# Top.net
KiCad netlist of a schematic drawn in Altium Designer
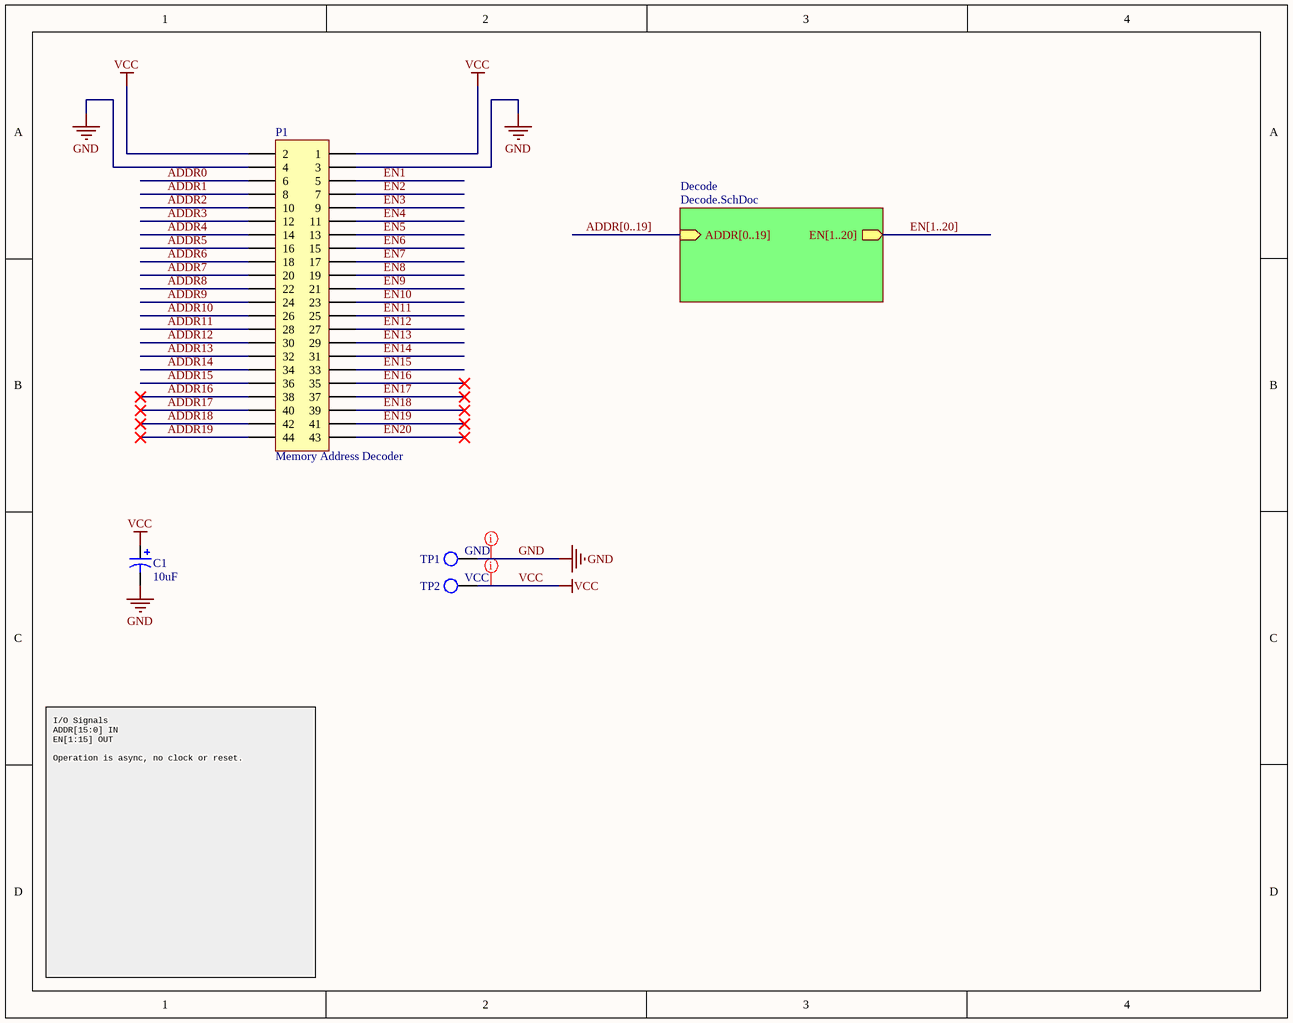
[diagram p0: Top.SchDoc]

(export (version "E")
  (design (tool "Eeschema 10.0.6"))
  (components
    (comp (ref "C1")
      (value "10uF")
      (footprint "C5x7")
      (description "Polarized Capacitor")
      (fields (field (name "Comment") "Cap Pol5") (field (name "PUBLISHER") "Altium Limited"))
      (libsource (lib "Miscellaneous Devices") (part "Cap Pol5"))
    )
    (comp (ref "P1")
      (value "Memory Address Decoder")
      (footprint "HDR2X22H")
      (description "Header, 22-Pin, Dual row, Right Angle")
      (fields (field (name "PUBLISHER") "Altium Limited"))
      (libsource (lib "Miscellaneous Connectors") (part "Header 22X2H"))
    )
    (comp (ref "TP1") (value "GND") (footprint "KSTN-5011_V") (libsource (lib "TP") (part "TP")))
    (comp (ref "TP2") (value "VCC") (footprint "KSTN-5011_V") (libsource (lib "TP") (part "TP")))
  )
  (nets
    (net (code "1") (name "/ADDR0") (class "Default")
      (node (ref "P1") (pin "6") (pinfunction "6_6") (pintype "passive"))
    )
    (net (code "2") (name "/ADDR1") (class "Default")
      (node (ref "P1") (pin "8") (pinfunction "8_8") (pintype "passive"))
    )
    (net (code "3") (name "/ADDR2") (class "Default")
      (node (ref "P1") (pin "10") (pinfunction "10_10") (pintype "passive"))
    )
    (net (code "4") (name "/ADDR3") (class "Default")
      (node (ref "P1") (pin "12") (pinfunction "12_12") (pintype "passive"))
    )
    (net (code "5") (name "/ADDR4") (class "Default")
      (node (ref "P1") (pin "14") (pinfunction "14_14") (pintype "passive"))
    )
    (net (code "6") (name "/ADDR5") (class "Default")
      (node (ref "P1") (pin "16") (pinfunction "16_16") (pintype "passive"))
    )
    (net (code "7") (name "/ADDR6") (class "Default")
      (node (ref "P1") (pin "18") (pinfunction "18_18") (pintype "passive"))
    )
    (net (code "8") (name "/ADDR7") (class "Default")
      (node (ref "P1") (pin "20") (pinfunction "20_20") (pintype "passive"))
    )
    (net (code "9") (name "/ADDR8") (class "Default")
      (node (ref "P1") (pin "22") (pinfunction "22_22") (pintype "passive"))
    )
    (net (code "10") (name "/ADDR9") (class "Default")
      (node (ref "P1") (pin "24") (pinfunction "24_24") (pintype "passive"))
    )
    (net (code "11") (name "/ADDR10") (class "Default")
      (node (ref "P1") (pin "26") (pinfunction "26_26") (pintype "passive"))
    )
    (net (code "12") (name "/ADDR11") (class "Default")
      (node (ref "P1") (pin "28") (pinfunction "28_28") (pintype "passive"))
    )
    (net (code "13") (name "/ADDR12") (class "Default")
      (node (ref "P1") (pin "30") (pinfunction "30_30") (pintype "passive"))
    )
    (net (code "14") (name "/ADDR13") (class "Default")
      (node (ref "P1") (pin "32") (pinfunction "32_32") (pintype "passive"))
    )
    (net (code "15") (name "/ADDR14") (class "Default")
      (node (ref "P1") (pin "34") (pinfunction "34_34") (pintype "passive"))
    )
    (net (code "16") (name "/ADDR15") (class "Default")
      (node (ref "P1") (pin "36") (pinfunction "36_36") (pintype "passive"))
    )
    (net (code "17") (name "/ADDR16") (class "Default")
      (node (ref "P1") (pin "38") (pinfunction "38_38") (pintype "passive+no_connect"))
    )
    (net (code "18") (name "/ADDR17") (class "Default")
      (node (ref "P1") (pin "40") (pinfunction "40_40") (pintype "passive+no_connect"))
    )
    (net (code "19") (name "/ADDR18") (class "Default")
      (node (ref "P1") (pin "42") (pinfunction "42_42") (pintype "passive+no_connect"))
    )
    (net (code "20") (name "/ADDR19") (class "Default")
      (node (ref "P1") (pin "44") (pinfunction "44_44") (pintype "passive+no_connect"))
    )
    (net (code "22") (name "/EN1") (class "Default")
      (node (ref "P1") (pin "5") (pinfunction "5_5") (pintype "passive"))
    )
    (net (code "23") (name "/EN2") (class "Default")
      (node (ref "P1") (pin "7") (pinfunction "7_7") (pintype "passive"))
    )
    (net (code "24") (name "/EN3") (class "Default")
      (node (ref "P1") (pin "9") (pinfunction "9_9") (pintype "passive"))
    )
    (net (code "25") (name "/EN4") (class "Default")
      (node (ref "P1") (pin "11") (pinfunction "11_11") (pintype "passive"))
    )
    (net (code "26") (name "/EN5") (class "Default")
      (node (ref "P1") (pin "13") (pinfunction "13_13") (pintype "passive"))
    )
    (net (code "27") (name "/EN6") (class "Default")
      (node (ref "P1") (pin "15") (pinfunction "15_15") (pintype "passive"))
    )
    (net (code "28") (name "/EN7") (class "Default")
      (node (ref "P1") (pin "17") (pinfunction "17_17") (pintype "passive"))
    )
    (net (code "29") (name "/EN8") (class "Default")
      (node (ref "P1") (pin "19") (pinfunction "19_19") (pintype "passive"))
    )
    (net (code "30") (name "/EN9") (class "Default")
      (node (ref "P1") (pin "21") (pinfunction "21_21") (pintype "passive"))
    )
    (net (code "31") (name "/EN10") (class "Default")
      (node (ref "P1") (pin "23") (pinfunction "23_23") (pintype "passive"))
    )
    (net (code "32") (name "/EN11") (class "Default")
      (node (ref "P1") (pin "25") (pinfunction "25_25") (pintype "passive"))
    )
    (net (code "33") (name "/EN12") (class "Default")
      (node (ref "P1") (pin "27") (pinfunction "27_27") (pintype "passive"))
    )
    (net (code "34") (name "/EN13") (class "Default")
      (node (ref "P1") (pin "29") (pinfunction "29_29") (pintype "passive"))
    )
    (net (code "35") (name "/EN14") (class "Default")
      (node (ref "P1") (pin "31") (pinfunction "31_31") (pintype "passive"))
    )
    (net (code "36") (name "/EN15") (class "Default")
      (node (ref "P1") (pin "33") (pinfunction "33_33") (pintype "passive"))
    )
    (net (code "37") (name "/EN16") (class "Default")
      (node (ref "P1") (pin "35") (pinfunction "35_35") (pintype "passive+no_connect"))
    )
    (net (code "38") (name "/EN17") (class "Default")
      (node (ref "P1") (pin "37") (pinfunction "37_37") (pintype "passive+no_connect"))
    )
    (net (code "39") (name "/EN18") (class "Default")
      (node (ref "P1") (pin "39") (pinfunction "39_39") (pintype "passive+no_connect"))
    )
    (net (code "40") (name "/EN19") (class "Default")
      (node (ref "P1") (pin "41") (pinfunction "41_41") (pintype "passive+no_connect"))
    )
    (net (code "41") (name "/EN20") (class "Default")
      (node (ref "P1") (pin "43") (pinfunction "43_43") (pintype "passive+no_connect"))
    )
    (net (code "43") (name "GND") (class "Default")
      (node (ref "C1") (pin "2") (pinfunction "2_2") (pintype "passive"))
      (node (ref "P1") (pin "3") (pinfunction "3_3") (pintype "passive"))
      (node (ref "P1") (pin "4") (pinfunction "4_4") (pintype "passive"))
      (node (ref "TP1") (pin "1") (pintype "passive"))
    )
    (net (code "44") (name "VCC") (class "Default")
      (node (ref "C1") (pin "1") (pinfunction "1_1") (pintype "passive"))
      (node (ref "P1") (pin "1") (pinfunction "1_1") (pintype "passive"))
      (node (ref "P1") (pin "2") (pinfunction "2_2") (pintype "passive"))
      (node (ref "TP2") (pin "1") (pintype "passive"))
    )
  )
)
